# integrater.net
KiCad netlist of a schematic drawn in Altium Designer
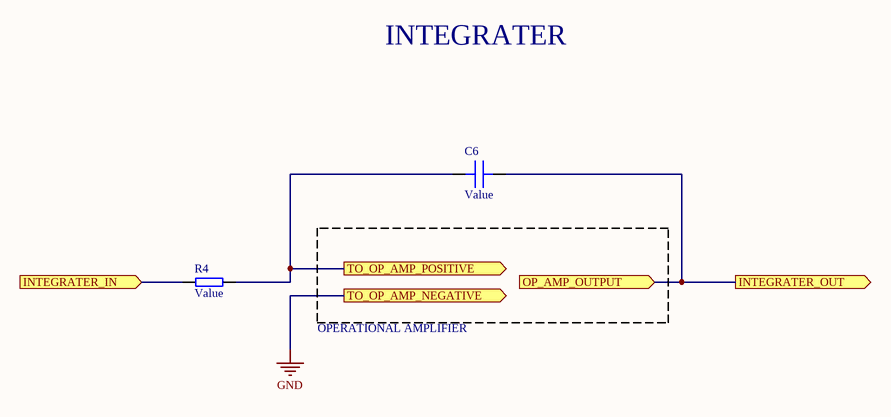
[diagram p0: integrater.SchDoc]

(export (version "E")
  (design (tool "Eeschema 10.0.6"))
  (components
    (comp (ref "C6")
      (value "Value")
      (footprint "C 0402")
      (description "MLCC Capacitor")
      (libsource (lib "Components") (part "Capacitor"))
    )
    (comp (ref "R4")
      (value "Value")
      (footprint "R 0402")
      (description "General pourpouse resistor")
      (libsource (lib "Components") (part "Resistor"))
    )
  )
  (nets
    (net (code "1") (name "/INTEGRATER_IN") (class "Default")
      (node (ref "R4") (pin "2") (pinfunction "2_2") (pintype "passive"))
    )
    (net (code "2") (name "/INTEGRATER_OUT") (class "Default")
      (node (ref "C6") (pin "2") (pinfunction "2_2") (pintype "passive"))
    )
    (net (code "3") (name "/TO_OP_AMP_POSITIVE") (class "Default")
      (node (ref "C6") (pin "1") (pinfunction "1_1") (pintype "passive"))
      (node (ref "R4") (pin "1") (pinfunction "1_1") (pintype "passive"))
    )
  )
)
